# CAN.net
KiCad netlist of a schematic drawn in Altium Designer
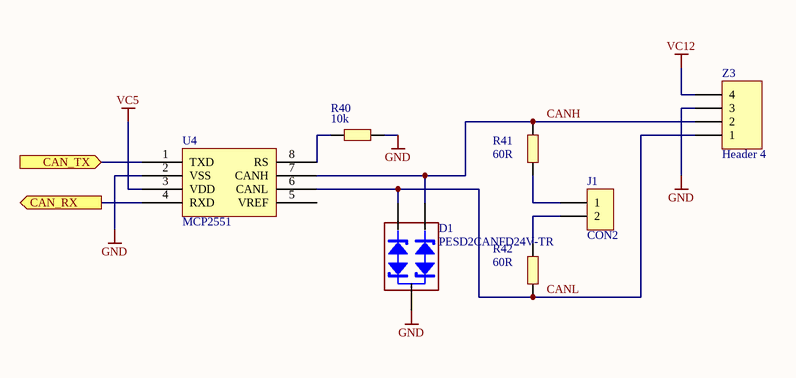
[diagram p0: CAN.SchDoc]

(export (version "E")
  (design (tool "Eeschema 10.0.6"))
  (components
    (comp (ref "D1")
      (value "PESD2CANFD24V-TR")
      (footprint "SOT23")
      (libsource (lib "GkSchlib") (part "PESD2CANFD24V-TR"))
    )
    (comp (ref "J1")
      (value "CON2")
      (footprint "PIN2")
      (description "Connector")
      (libsource (lib "*") (part "CON2"))
    )
    (comp (ref "R40") (value "10k") (footprint "0603R") (libsource (lib "") (part "RES3_1")))
    (comp (ref "R41") (value "60R") (footprint "1206") (libsource (lib "*") (part "RES3")))
    (comp (ref "R42") (value "60R") (footprint "1206") (libsource (lib "*") (part "RES3")))
    (comp (ref "U4") (value "MCP2551") (footprint "SO8") (libsource (lib "*") (part "MCP2551")))
    (comp (ref "Z3")
      (value "Header 4")
      (footprint "JST-B4B-XH-A")
      (description "Header, 4-Pin")
      (fields (field (name "PUBLISHER") "Altium Limited"))
      (libsource (lib "Miscellaneous Connectors") (part "Header 4"))
    )
  )
  (nets
    (net (code "1") (name "/CANH") (class "Default")
      (node (ref "D1") (pin "1") (pinfunction "K1_1") (pintype "passive"))
      (node (ref "R41") (pin "2") (pintype "passive"))
      (node (ref "U4") (pin "7") (pinfunction "CANH_7") (pintype "passive"))
      (node (ref "Z3") (pin "2") (pinfunction "2_2") (pintype "passive"))
    )
    (net (code "2") (name "/CANL") (class "Default")
      (node (ref "D1") (pin "2") (pinfunction "K2_2") (pintype "passive"))
      (node (ref "R42") (pin "1") (pintype "passive"))
      (node (ref "U4") (pin "6") (pinfunction "CANL_6") (pintype "passive"))
      (node (ref "Z3") (pin "1") (pinfunction "1_1") (pintype "passive"))
    )
    (net (code "3") (name "/CAN_RX") (class "Default")
      (node (ref "U4") (pin "4") (pinfunction "RXD_4") (pintype "passive"))
    )
    (net (code "4") (name "/CAN_TX") (class "Default")
      (node (ref "U4") (pin "1") (pinfunction "TXD_1") (pintype "passive"))
    )
    (net (code "5") (name "GND") (class "Default")
      (node (ref "D1") (pin "3") (pinfunction "CC_3") (pintype "passive"))
      (node (ref "R40") (pin "2") (pintype "passive"))
      (node (ref "U4") (pin "2") (pinfunction "VSS_2") (pintype "passive"))
      (node (ref "Z3") (pin "3") (pinfunction "3_3") (pintype "passive"))
    )
    (net (code "6") (name "Net-(J1-Pad1)") (class "Default")
      (node (ref "J1") (pin "1") (pinfunction "1_1") (pintype "passive"))
      (node (ref "R41") (pin "1") (pintype "passive"))
    )
    (net (code "7") (name "Net-(J1-Pad2)") (class "Default")
      (node (ref "J1") (pin "2") (pinfunction "2_2") (pintype "passive"))
      (node (ref "R42") (pin "2") (pintype "passive"))
    )
    (net (code "8") (name "Net-(U4-RS)") (class "Default")
      (node (ref "R40") (pin "1") (pintype "passive"))
      (node (ref "U4") (pin "8") (pinfunction "RS_8") (pintype "passive"))
    )
    (net (code "9") (name "VC5") (class "Default")
      (node (ref "U4") (pin "3") (pinfunction "VDD_3") (pintype "passive"))
    )
    (net (code "10") (name "VC12") (class "Default")
      (node (ref "Z3") (pin "4") (pinfunction "4_4") (pintype "passive"))
    )
    (net (code "11") (name "unconnected-(U4-VREF-Pad5)") (class "Default")
      (node (ref "U4") (pin "5") (pinfunction "VREF_5") (pintype "passive"))
    )
  )
)
